# main.net
KiCad netlist of a schematic drawn in EAGLE
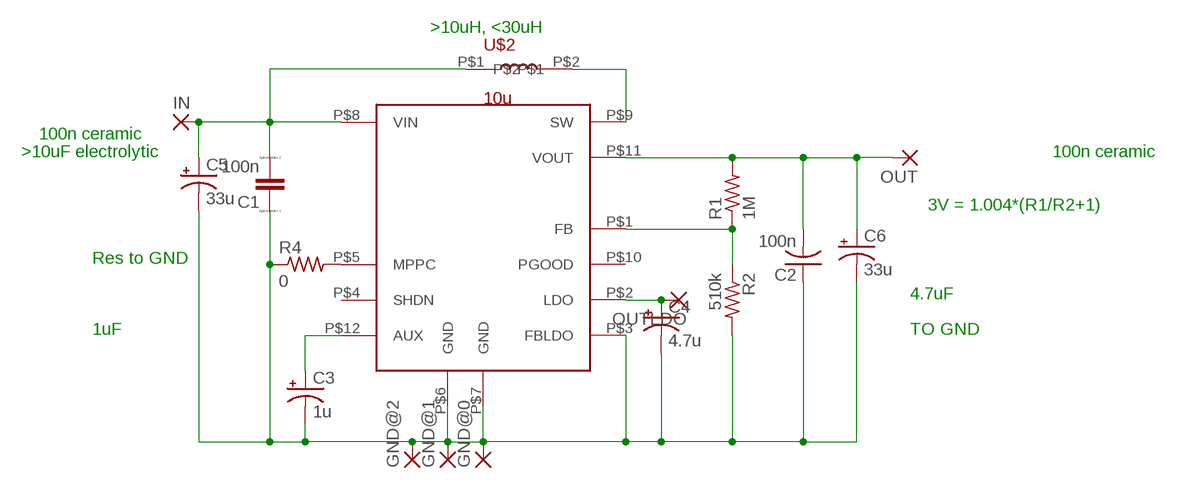
[diagram p0: schematic, sheet 1]

(export (version "E")
  (design (tool "Eeschema 10.0.6"))
  (components
    (comp (ref "C1")
      (value "100n")
      (footprint "eagle-import:C0603")
      (libsource (lib "eagle-import") (part "CC0603"))
    )
    (comp (ref "C2")
      (value "100n")
      (footprint "eagle-import:C025-025X050")
      (libsource (lib "eagle-import") (part "C-US025-025X050"))
    )
    (comp (ref "C3")
      (value "1u")
      (footprint "eagle-import:E1,8-4")
      (libsource (lib "eagle-import") (part "CPOL-USE1.8-4"))
    )
    (comp (ref "C4")
      (value "4.7u")
      (footprint "eagle-import:E1,8-4")
      (libsource (lib "eagle-import") (part "CPOL-USE1.8-4"))
    )
    (comp (ref "C5")
      (value "33u")
      (footprint "eagle-import:E2-5")
      (libsource (lib "eagle-import") (part "CPOL-USE2-5"))
    )
    (comp (ref "C6")
      (value "33u")
      (footprint "eagle-import:E2-5")
      (libsource (lib "eagle-import") (part "CPOL-USE2-5"))
    )
    (comp (ref "GND@0")
      (value "2,54/1,0")
      (footprint "eagle-import:2,54_1,0")
      (libsource (lib "eagle-import") (part "2,54/1,0"))
    )
    (comp (ref "GND@1")
      (value "2,54/1,0")
      (footprint "eagle-import:2,54_1,0")
      (libsource (lib "eagle-import") (part "2,54/1,0"))
    )
    (comp (ref "GND@2")
      (value "2,54/1,0")
      (footprint "eagle-import:2,54_1,0")
      (libsource (lib "eagle-import") (part "2,54/1,0"))
    )
    (comp (ref "IN")
      (value "2,54/1,0")
      (footprint "eagle-import:2,54_1,0")
      (libsource (lib "eagle-import") (part "2,54/1,0"))
    )
    (comp (ref "OUT")
      (value "2,54/1,0")
      (footprint "eagle-import:2,54_1,0")
      (libsource (lib "eagle-import") (part "2,54/1,0"))
    )
    (comp (ref "OUTLDO")
      (value "2,54/1,0")
      (footprint "eagle-import:2,54_1,0")
      (libsource (lib "eagle-import") (part "2,54/1,0"))
    )
    (comp (ref "R1")
      (value "1M")
      (footprint "eagle-import:0204V")
      (libsource (lib "eagle-import") (part "R-US_0204/2V"))
    )
    (comp (ref "R2")
      (value "510k")
      (footprint "eagle-import:R0603")
      (libsource (lib "eagle-import") (part "R-US_R0603"))
    )
    (comp (ref "R4")
      (value "0")
      (footprint "eagle-import:R0603")
      (libsource (lib "eagle-import") (part "R-US_R0603"))
    )
    (comp (ref "U$1")
      (value "LTC3105")
      (footprint "eagle-import:MSOP_12")
      (libsource (lib "eagle-import") (part "LTC3105"))
    )
    (comp (ref "U$2")
      (value "10u")
      (footprint "eagle-import:DR0810")
      (libsource (lib "eagle-import") (part "DR0810"))
    )
  )
  (nets
    (net (code "1") (name "Net-(GND@0-P)") (class "Default")
      (node (ref "C1") (pin "1") (pinfunction "1_1") (pintype "passive"))
      (node (ref "C2") (pin "1") (pinfunction "1_1") (pintype "passive"))
      (node (ref "C3") (pin "-") (pinfunction "-_-") (pintype "passive"))
      (node (ref "C4") (pin "-") (pinfunction "-_-") (pintype "passive"))
      (node (ref "C5") (pin "-") (pinfunction "-_-") (pintype "passive"))
      (node (ref "C6") (pin "-") (pinfunction "-_-") (pintype "passive"))
      (node (ref "GND@0") (pin "1") (pinfunction "P_1") (pintype "passive"))
      (node (ref "GND@1") (pin "1") (pinfunction "P_1") (pintype "passive"))
      (node (ref "GND@2") (pin "1") (pinfunction "P_1") (pintype "passive"))
      (node (ref "R2") (pin "2") (pinfunction "2_2") (pintype "passive"))
      (node (ref "R4") (pin "1") (pinfunction "1_1") (pintype "passive"))
      (node (ref "U$1") (pin "P$3") (pinfunction "FBLDO_P$3") (pintype "bidirectional"))
      (node (ref "U$1") (pin "P$6") (pinfunction "GND_P$6") (pintype "bidirectional"))
      (node (ref "U$1") (pin "P$7") (pinfunction "GND_P$7") (pintype "bidirectional"))
    )
    (net (code "2") (name "Net-(IN-P)") (class "Default")
      (node (ref "C1") (pin "2") (pinfunction "2_2") (pintype "passive"))
      (node (ref "C5") (pin "+") (pinfunction "+_+") (pintype "passive"))
      (node (ref "IN") (pin "1") (pinfunction "P_1") (pintype "passive"))
      (node (ref "U$1") (pin "P$8") (pinfunction "VIN_P$8") (pintype "bidirectional"))
      (node (ref "U$2") (pin "P$1") (pinfunction "P$1_P$1") (pintype "bidirectional"))
    )
    (net (code "3") (name "Net-(OUT-P)") (class "Default")
      (node (ref "C2") (pin "2") (pinfunction "2_2") (pintype "passive"))
      (node (ref "C6") (pin "+") (pinfunction "+_+") (pintype "passive"))
      (node (ref "OUT") (pin "1") (pinfunction "P_1") (pintype "passive"))
      (node (ref "R1") (pin "2") (pinfunction "2_2") (pintype "passive"))
      (node (ref "U$1") (pin "P$11") (pinfunction "VOUT_P$11") (pintype "bidirectional"))
    )
    (net (code "4") (name "Net-(OUTLDO-P)") (class "Default")
      (node (ref "C4") (pin "+") (pinfunction "+_+") (pintype "passive"))
      (node (ref "OUTLDO") (pin "1") (pinfunction "P_1") (pintype "passive"))
      (node (ref "U$1") (pin "P$2") (pinfunction "LDO_P$2") (pintype "bidirectional"))
    )
    (net (code "5") (name "Net-(U$1-AUX)") (class "Default")
      (node (ref "C3") (pin "+") (pinfunction "+_+") (pintype "passive"))
      (node (ref "U$1") (pin "P$12") (pinfunction "AUX_P$12") (pintype "bidirectional"))
    )
    (net (code "6") (name "Net-(U$1-FB)") (class "Default")
      (node (ref "R1") (pin "1") (pinfunction "1_1") (pintype "passive"))
      (node (ref "R2") (pin "1") (pinfunction "1_1") (pintype "passive"))
      (node (ref "U$1") (pin "P$1") (pinfunction "FB_P$1") (pintype "bidirectional"))
    )
    (net (code "7") (name "Net-(U$1-MPPC)") (class "Default")
      (node (ref "R4") (pin "2") (pinfunction "2_2") (pintype "passive"))
      (node (ref "U$1") (pin "P$5") (pinfunction "MPPC_P$5") (pintype "bidirectional"))
    )
    (net (code "8") (name "Net-(U$1-SW)") (class "Default")
      (node (ref "U$1") (pin "P$9") (pinfunction "SW_P$9") (pintype "bidirectional"))
      (node (ref "U$2") (pin "P$2") (pinfunction "P$2_P$2") (pintype "bidirectional"))
    )
    (net (code "9") (name "unconnected-(U$1-PGOOD-PadP$10)") (class "Default")
      (node (ref "U$1") (pin "P$10") (pinfunction "PGOOD_P$10") (pintype "bidirectional"))
    )
    (net (code "10") (name "unconnected-(U$1-SHDN-PadP$4)") (class "Default")
      (node (ref "U$1") (pin "P$4") (pinfunction "SHDN_P$4") (pintype "bidirectional"))
    )
  )
)
